# Power.net
KiCad netlist of a schematic drawn in Altium Designer
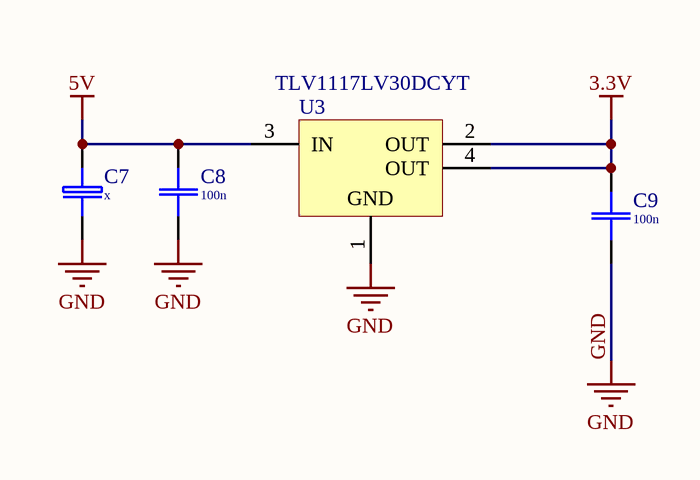
[diagram p0: Power.SchDoc]

(export (version "E")
  (design (tool "Eeschema 10.0.6"))
  (components
    (comp (ref "C7")
      (value "x")
      (footprint "EL Case C (6032-28)")
      (description "EL Tantalum Case C (6032-28)")
      (libsource (lib "SMD-RCL") (part "EL Case C (6032-28)"))
    )
    (comp (ref "C8")
      (value "100n")
      (footprint "C0805(2013)")
      (description "SMD-0805 50V Y5V +80/-20%")
      (libsource (lib "SMD-RCL") (part "C-0805   50V 100n"))
    )
    (comp (ref "C9")
      (value "100n")
      (footprint "C0805(2013)")
      (description "SMD-0805 50V Y5V +80/-20%")
      (libsource (lib "SMD-RCL") (part "C-0805   50V 100n"))
    )
    (comp (ref "U3")
      (value "TLV1117LV30DCYT")
      (footprint "TI-DCY4_N")
      (fields (field (name "MANUFACTURER") "Texas Instruments"))
      (libsource (lib "TI Power Management Linear Regulator Single Channel LDO (400-7500mA)") (part "TLV1117LV30DCYT"))
    )
  )
  (nets
    (net (code "1") (name "3.3V") (class "Default")
      (node (ref "C9") (pin "2") (pinfunction "2_2") (pintype "passive"))
      (node (ref "U3") (pin "2") (pinfunction "OUT_2") (pintype "power_in"))
      (node (ref "U3") (pin "4") (pinfunction "OUT_4") (pintype "power_in"))
    )
    (net (code "2") (name "5V") (class "Default")
      (node (ref "C7") (pin "1") (pinfunction "+_1") (pintype "passive"))
      (node (ref "C8") (pin "2") (pinfunction "2_2") (pintype "passive"))
      (node (ref "U3") (pin "3") (pinfunction "IN_3") (pintype "power_in"))
    )
    (net (code "3") (name "GND") (class "Default")
      (node (ref "C7") (pin "2") (pinfunction "-_2") (pintype "passive"))
      (node (ref "C8") (pin "1") (pinfunction "1_1") (pintype "passive"))
      (node (ref "C9") (pin "1") (pinfunction "1_1") (pintype "passive"))
      (node (ref "U3") (pin "1") (pinfunction "GND_1") (pintype "power_in"))
    )
  )
)
